# doogie_bottom_board.net
KiCad netlist of a schematic drawn in EAGLE
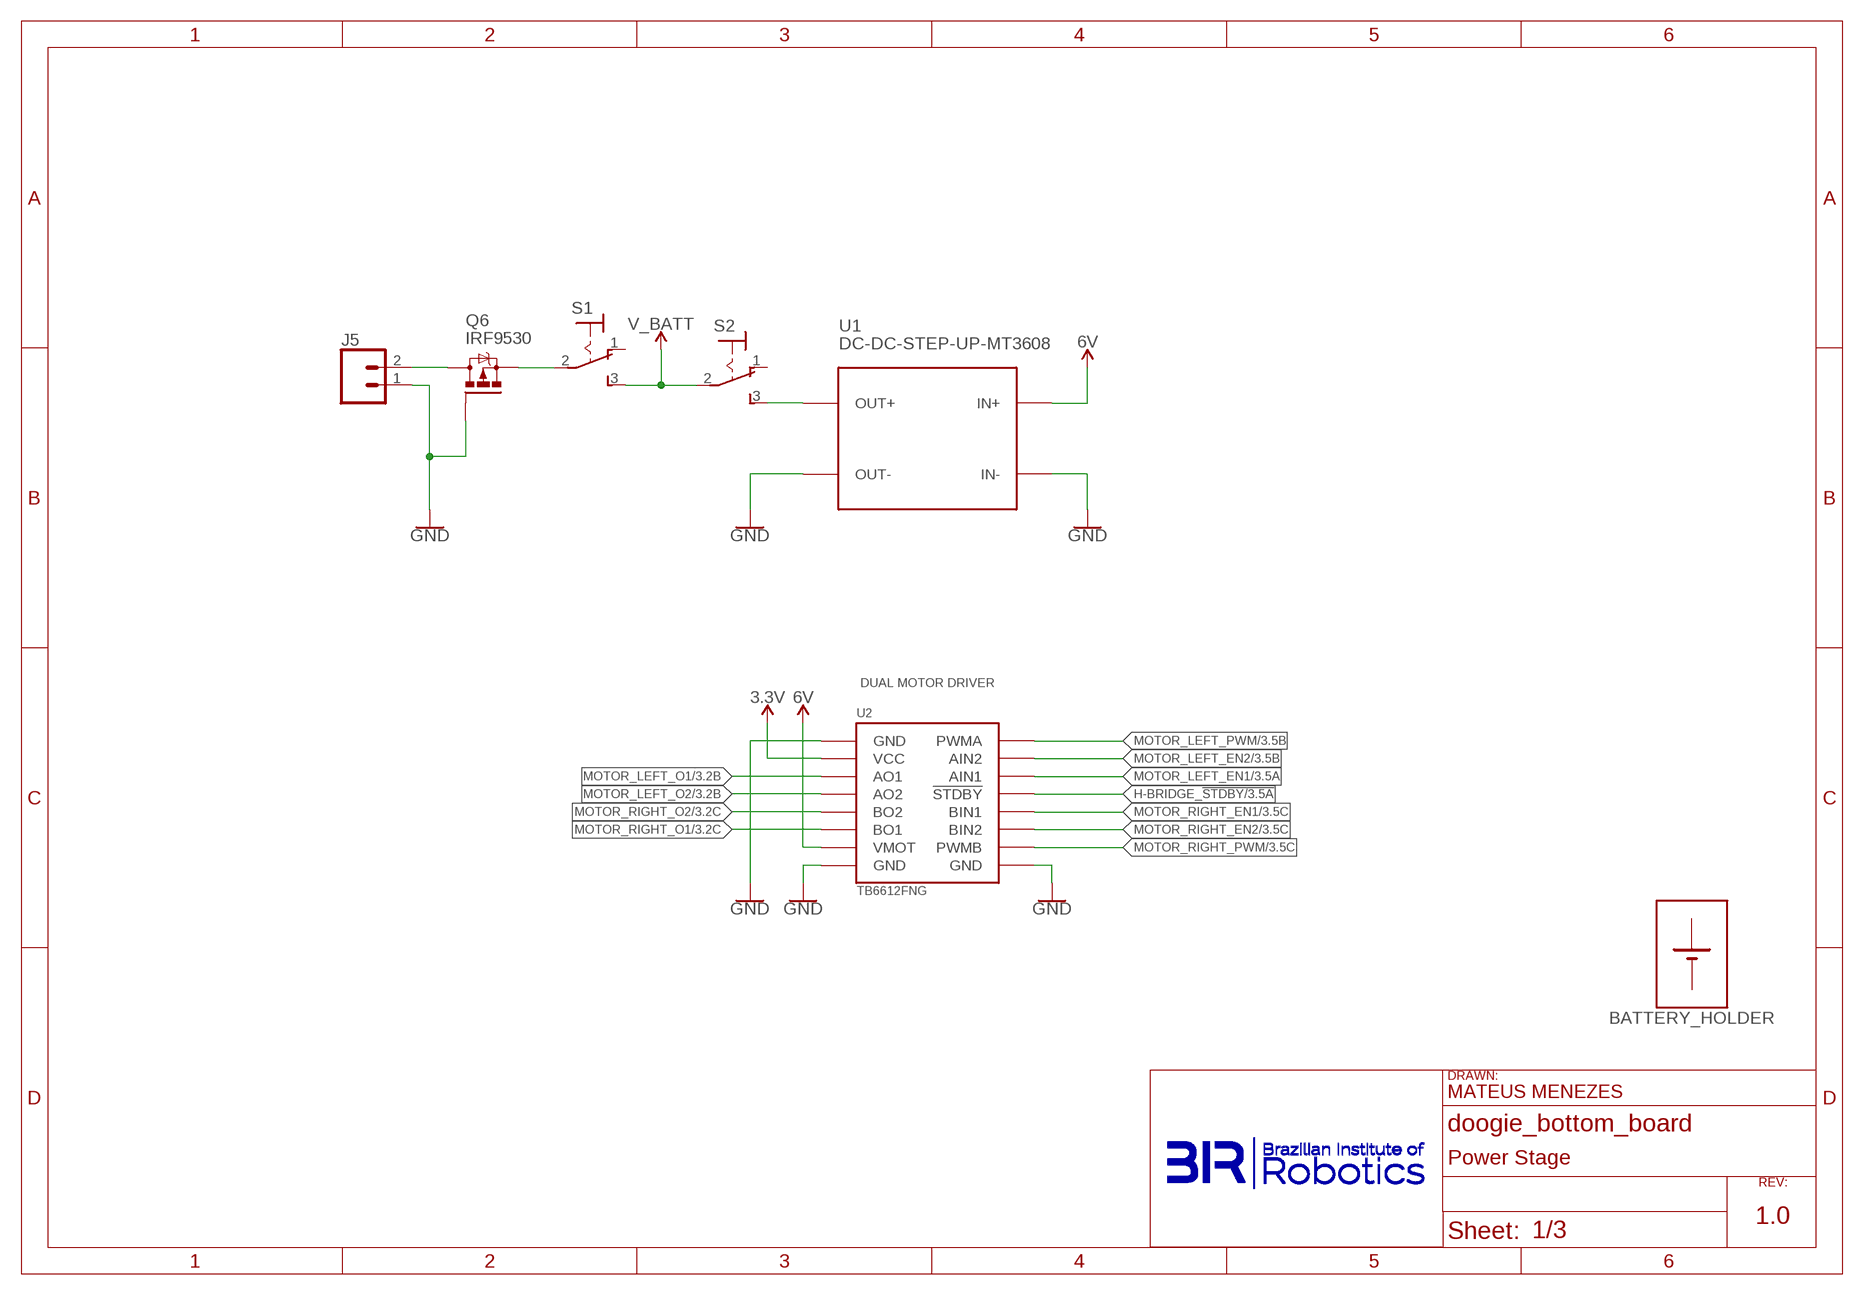
[diagram p0: schematic, sheet 1]
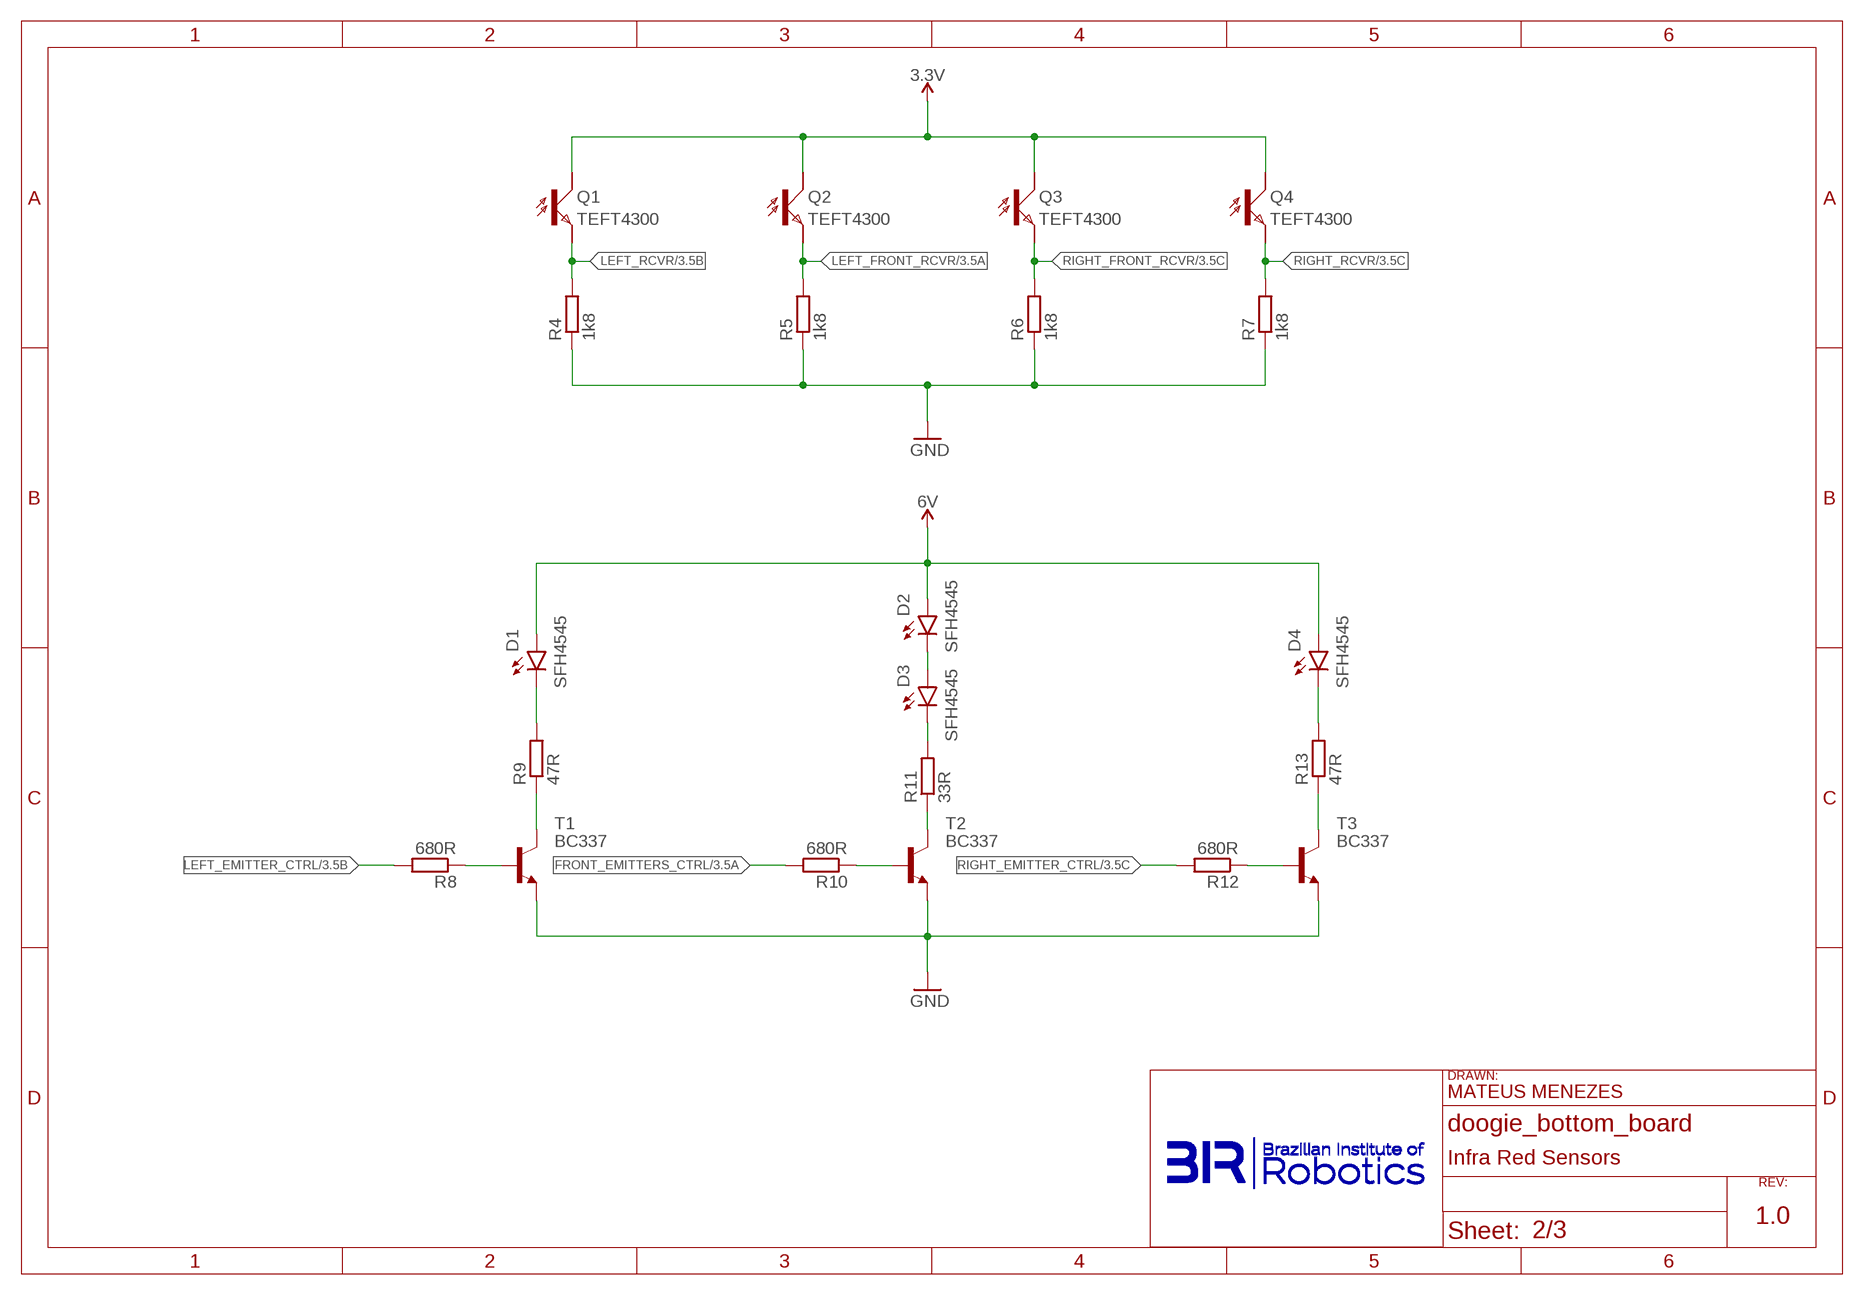
[diagram p1: schematic, sheet 2]
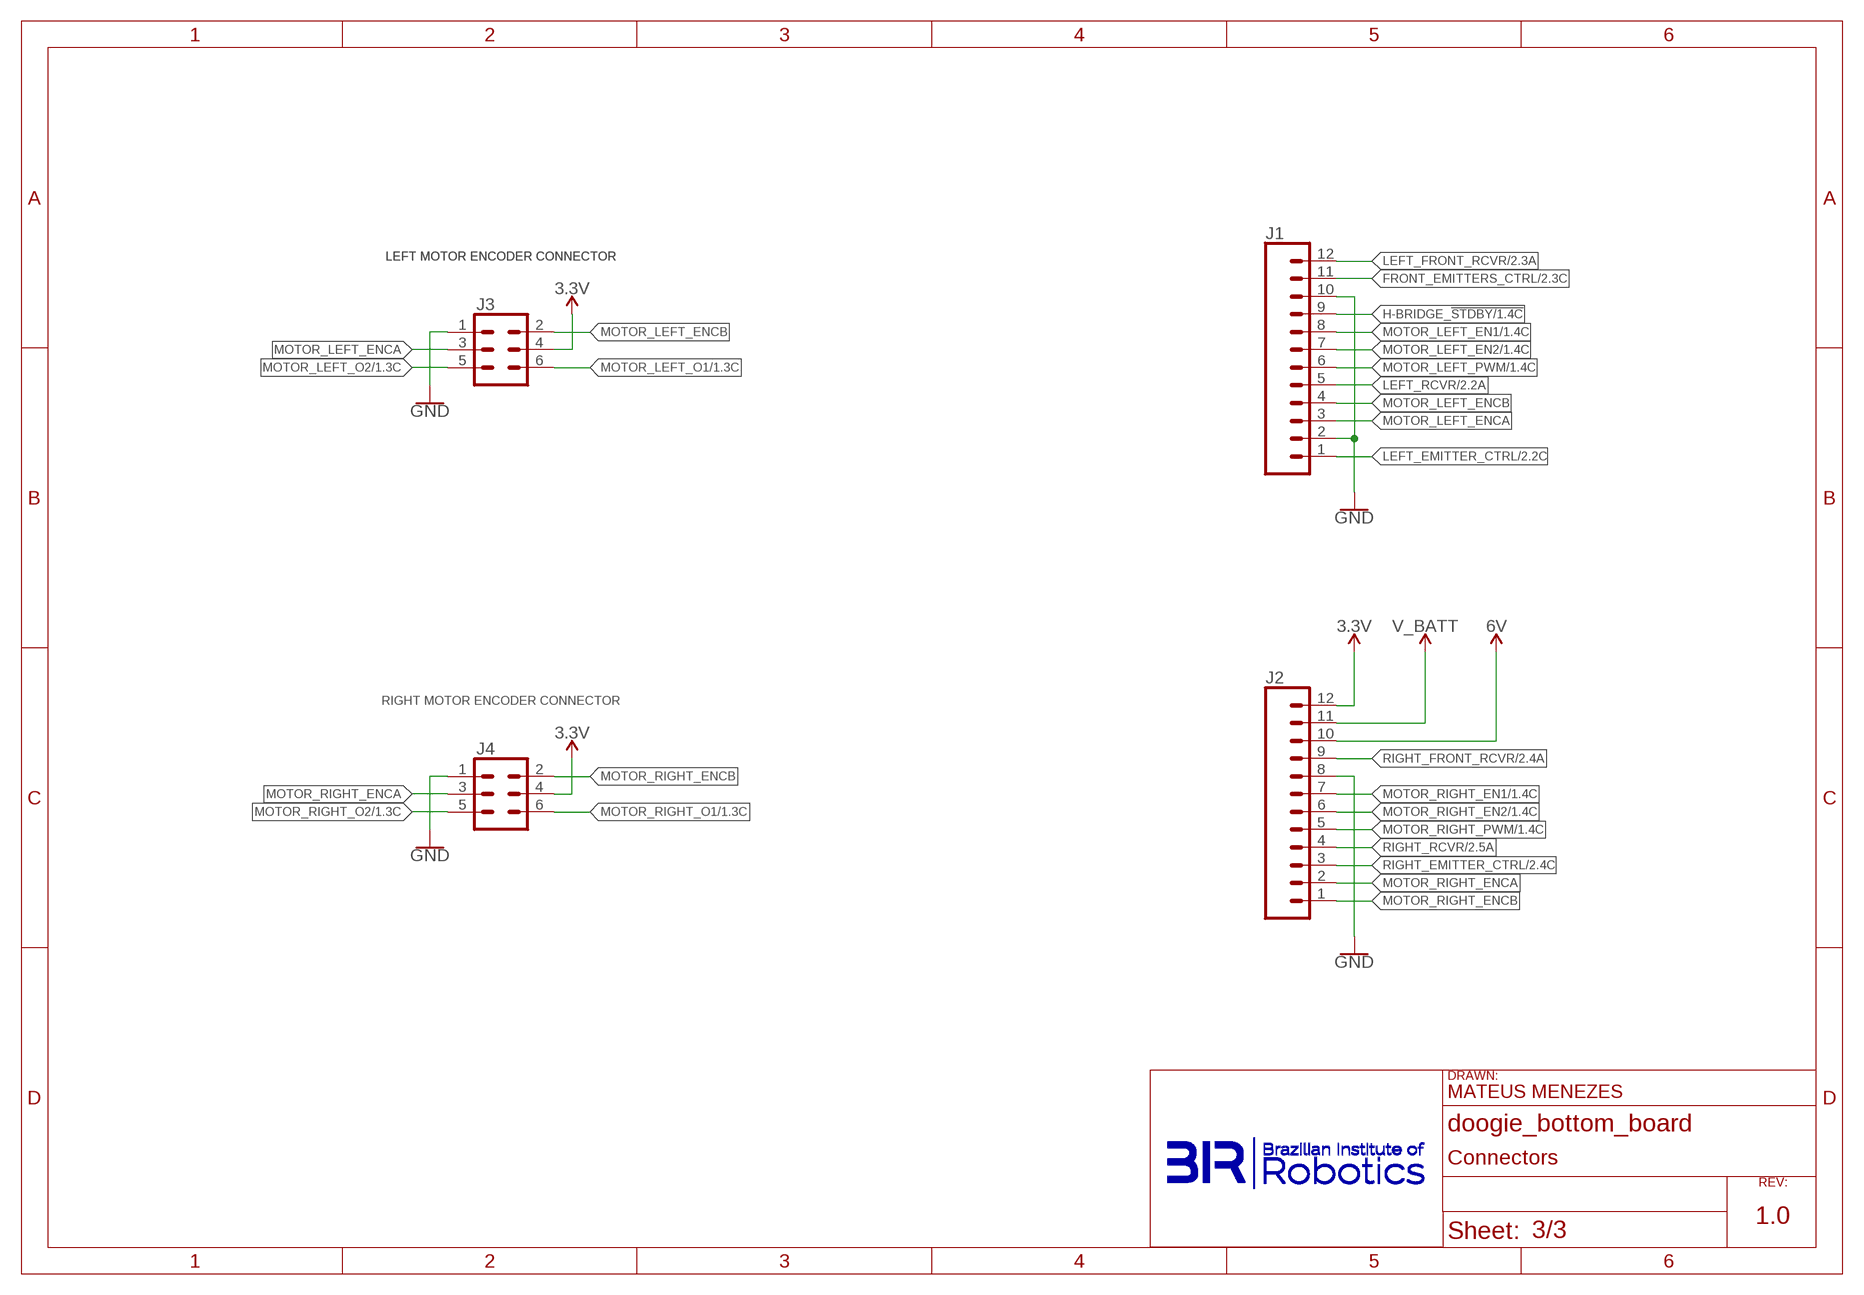
[diagram p2: schematic, sheet 3]

(export (version "E")
  (design (tool "Eeschema 10.0.6"))
  (components
    (comp (ref "D1")
      (value "SFH4545")
      (footprint "eagle-import:SFH4545-AK")
      (libsource (lib "eagle-import") (part "SFH4545"))
    )
    (comp (ref "D2")
      (value "SFH4545")
      (footprint "eagle-import:SFH4545-AK")
      (libsource (lib "eagle-import") (part "SFH4545"))
    )
    (comp (ref "D3")
      (value "SFH4545")
      (footprint "eagle-import:SFH4545-AK")
      (libsource (lib "eagle-import") (part "SFH4545"))
    )
    (comp (ref "D4")
      (value "SFH4545")
      (footprint "eagle-import:SFH4545-AK")
      (libsource (lib "eagle-import") (part "SFH4545"))
    )
    (comp (ref "Q1")
      (value "TEFT4300")
      (footprint "eagle-import:TEFT_5MM_RA")
      (libsource (lib "eagle-import") (part "TEFT4300_5MM_RA"))
    )
    (comp (ref "Q2")
      (value "TEFT4300")
      (footprint "eagle-import:TEFT_5MM_RA")
      (libsource (lib "eagle-import") (part "TEFT4300_5MM_RA"))
    )
    (comp (ref "Q3")
      (value "TEFT4300")
      (footprint "eagle-import:TEFT_5MM_RA")
      (libsource (lib "eagle-import") (part "TEFT4300_5MM_RA"))
    )
    (comp (ref "Q4")
      (value "TEFT4300")
      (footprint "eagle-import:TEFT_5MM_RA")
      (libsource (lib "eagle-import") (part "TEFT4300_5MM_RA"))
    )
    (comp (ref "R4")
      (value "1k8")
      (footprint "eagle-import:0204_7")
      (libsource (lib "eagle-import") (part "R-EU_0204/7"))
    )
    (comp (ref "R5")
      (value "1k8")
      (footprint "eagle-import:0204_7")
      (libsource (lib "eagle-import") (part "R-EU_0204/7"))
    )
    (comp (ref "R6")
      (value "1k8")
      (footprint "eagle-import:0204_7")
      (libsource (lib "eagle-import") (part "R-EU_0204/7"))
    )
    (comp (ref "R7")
      (value "1k8")
      (footprint "eagle-import:0204_7")
      (libsource (lib "eagle-import") (part "R-EU_0204/7"))
    )
    (comp (ref "R8")
      (value "680R")
      (footprint "eagle-import:0204_7")
      (libsource (lib "eagle-import") (part "R-EU_0204/7"))
    )
    (comp (ref "R9")
      (value "47R")
      (footprint "eagle-import:0204_7")
      (libsource (lib "eagle-import") (part "R-EU_0204/7"))
    )
    (comp (ref "R10")
      (value "680R")
      (footprint "eagle-import:0204_7")
      (libsource (lib "eagle-import") (part "R-EU_0204/7"))
    )
    (comp (ref "R11")
      (value "33R")
      (footprint "eagle-import:0204_7")
      (libsource (lib "eagle-import") (part "R-EU_0204/7"))
    )
    (comp (ref "R12")
      (value "680R")
      (footprint "eagle-import:0204_7")
      (libsource (lib "eagle-import") (part "R-EU_0204/7"))
    )
    (comp (ref "R13")
      (value "47R")
      (footprint "eagle-import:0204_7")
      (libsource (lib "eagle-import") (part "R-EU_0204/7"))
    )
    (comp (ref "T1")
      (value "BC337")
      (footprint "eagle-import:TO92")
      (libsource (lib "eagle-import") (part "BC337"))
    )
    (comp (ref "T2")
      (value "BC337")
      (footprint "eagle-import:TO92")
      (libsource (lib "eagle-import") (part "BC337"))
    )
    (comp (ref "T3")
      (value "BC337")
      (footprint "eagle-import:TO92")
      (libsource (lib "eagle-import") (part "BC337"))
    )
    (comp (ref "BATTERY_HOLDER")
      (value "BATTERY_HOLDER")
      (footprint "eagle-import:BATTERY_HOLDER")
      (libsource (lib "eagle-import") (part "BATTERY_HOLDER"))
    )
    (comp (ref "J5")
      (value "CONN_02JST-PTH-2")
      (footprint "eagle-import:JST-2-PTH")
      (libsource (lib "eagle-import") (part "CONN_02JST-PTH-2"))
    )
    (comp (ref "Q6")
      (value "IRF9530")
      (footprint "eagle-import:TO220BV")
      (libsource (lib "eagle-import") (part "IRF9530"))
    )
    (comp (ref "S1")
      (value "M9040P")
      (footprint "eagle-import:M9040P")
      (libsource (lib "eagle-import") (part "M9040P"))
    )
    (comp (ref "S2")
      (value "M9040P")
      (footprint "eagle-import:M9040P")
      (libsource (lib "eagle-import") (part "M9040P"))
    )
    (comp (ref "U1")
      (value "DC-DC-STEP-UP-MT3608")
      (footprint "eagle-import:DC-DC-STEP-UP-MT3608")
      (libsource (lib "eagle-import") (part "DC-DC-STEP-UP-MT3608"))
    )
    (comp (ref "U2")
      (value "TB6612FNG")
      (footprint "eagle-import:TB6612FNG")
      (libsource (lib "eagle-import") (part "TB6612FNG"))
    )
    (comp (ref "J1")
      (value "CONN_12")
      (footprint "eagle-import:1X12")
      (libsource (lib "eagle-import") (part "CONN_12"))
    )
    (comp (ref "J2")
      (value "CONN_12")
      (footprint "eagle-import:1X12")
      (libsource (lib "eagle-import") (part "CONN_12"))
    )
    (comp (ref "J3")
      (value "CONN_03X2SHROUD")
      (footprint "eagle-import:2X3-SHROUDED")
      (libsource (lib "eagle-import") (part "CONN_03X2SHROUD"))
    )
    (comp (ref "J4")
      (value "CONN_03X2SHROUD")
      (footprint "eagle-import:2X3-SHROUDED")
      (libsource (lib "eagle-import") (part "CONN_03X2SHROUD"))
    )
  )
  (nets
    (net (code "1") (name "3.3V") (class "Default")
      (node (ref "J2") (pin "12") (pinfunction "12_12") (pintype "passive"))
      (node (ref "J3") (pin "4") (pinfunction "4_4") (pintype "bidirectional"))
      (node (ref "J4") (pin "4") (pinfunction "4_4") (pintype "bidirectional"))
      (node (ref "Q1") (pin "C") (pinfunction "C_C") (pintype "passive"))
      (node (ref "Q2") (pin "C") (pinfunction "C_C") (pintype "passive"))
      (node (ref "Q3") (pin "C") (pinfunction "C_C") (pintype "passive"))
      (node (ref "Q4") (pin "C") (pinfunction "C_C") (pintype "passive"))
      (node (ref "U2") (pin "2") (pinfunction "VCC_2") (pintype "power_in"))
    )
    (net (code "2") (name "6V") (class "Default")
      (node (ref "D1") (pin "A") (pinfunction "A_A") (pintype "passive"))
      (node (ref "D2") (pin "A") (pinfunction "A_A") (pintype "passive"))
      (node (ref "D4") (pin "A") (pinfunction "A_A") (pintype "passive"))
      (node (ref "J2") (pin "10") (pinfunction "10_10") (pintype "passive"))
      (node (ref "U1") (pin "IN+") (pinfunction "IN+_IN+") (pintype "bidirectional"))
      (node (ref "U2") (pin "7") (pinfunction "VMOT_7") (pintype "power_in"))
    )
    (net (code "3") (name "FRONT_EMITTERS_CTRL") (class "Default")
      (node (ref "J1") (pin "11") (pinfunction "11_11") (pintype "passive"))
      (node (ref "R10") (pin "2") (pinfunction "2_2") (pintype "passive"))
    )
    (net (code "4") (name "GND") (class "Default")
      (node (ref "J1") (pin "10") (pinfunction "10_10") (pintype "passive"))
      (node (ref "J1") (pin "2") (pinfunction "2_2") (pintype "passive"))
      (node (ref "J2") (pin "8") (pinfunction "8_8") (pintype "passive"))
      (node (ref "J3") (pin "1") (pinfunction "1_1") (pintype "bidirectional"))
      (node (ref "J4") (pin "1") (pinfunction "1_1") (pintype "bidirectional"))
      (node (ref "J5") (pin "1") (pinfunction "1_1") (pintype "passive"))
      (node (ref "Q6") (pin "G") (pinfunction "G_G") (pintype "passive"))
      (node (ref "R4") (pin "1") (pinfunction "1_1") (pintype "passive"))
      (node (ref "R5") (pin "1") (pinfunction "1_1") (pintype "passive"))
      (node (ref "R6") (pin "1") (pinfunction "1_1") (pintype "passive"))
      (node (ref "R7") (pin "1") (pinfunction "1_1") (pintype "passive"))
      (node (ref "T1") (pin "1") (pinfunction "E_1") (pintype "passive"))
      (node (ref "T2") (pin "1") (pinfunction "E_1") (pintype "passive"))
      (node (ref "T3") (pin "1") (pinfunction "E_1") (pintype "passive"))
      (node (ref "U1") (pin "IN-") (pinfunction "IN-_IN-") (pintype "bidirectional"))
      (node (ref "U1") (pin "OUT-") (pinfunction "OUT-_OUT-") (pintype "bidirectional"))
      (node (ref "U2") (pin "1") (pinfunction "GND_1") (pintype "power_in"))
      (node (ref "U2") (pin "16") (pinfunction "GND_16") (pintype "power_in"))
      (node (ref "U2") (pin "8") (pinfunction "GND_8") (pintype "power_in"))
    )
    (net (code "5") (name "H-BRIDGE_~{STDBY}") (class "Default")
      (node (ref "J1") (pin "9") (pinfunction "9_9") (pintype "passive"))
      (node (ref "U2") (pin "12") (pinfunction "~{STDBY}_12") (pintype "input"))
    )
    (net (code "6") (name "LEFT_EMITTER_CTRL") (class "Default")
      (node (ref "J1") (pin "1") (pinfunction "1_1") (pintype "passive"))
      (node (ref "R8") (pin "2") (pinfunction "2_2") (pintype "passive"))
    )
    (net (code "7") (name "LEFT_FRONT_RCVR") (class "Default")
      (node (ref "J1") (pin "12") (pinfunction "12_12") (pintype "passive"))
      (node (ref "Q2") (pin "E") (pinfunction "E_E") (pintype "passive"))
      (node (ref "R5") (pin "2") (pinfunction "2_2") (pintype "passive"))
    )
    (net (code "8") (name "LEFT_RCVR") (class "Default")
      (node (ref "J1") (pin "5") (pinfunction "5_5") (pintype "passive"))
      (node (ref "Q1") (pin "E") (pinfunction "E_E") (pintype "passive"))
      (node (ref "R4") (pin "2") (pinfunction "2_2") (pintype "passive"))
    )
    (net (code "9") (name "MOTOR_LEFT_EN1") (class "Default")
      (node (ref "J1") (pin "8") (pinfunction "8_8") (pintype "passive"))
      (node (ref "U2") (pin "11") (pinfunction "AIN1_11") (pintype "input"))
    )
    (net (code "10") (name "MOTOR_LEFT_EN2") (class "Default")
      (node (ref "J1") (pin "7") (pinfunction "7_7") (pintype "passive"))
      (node (ref "U2") (pin "10") (pinfunction "AIN2_10") (pintype "input"))
    )
    (net (code "11") (name "MOTOR_LEFT_ENCA") (class "Default")
      (node (ref "J1") (pin "3") (pinfunction "3_3") (pintype "passive"))
      (node (ref "J3") (pin "3") (pinfunction "3_3") (pintype "bidirectional"))
    )
    (net (code "12") (name "MOTOR_LEFT_ENCB") (class "Default")
      (node (ref "J1") (pin "4") (pinfunction "4_4") (pintype "passive"))
      (node (ref "J3") (pin "2") (pinfunction "2_2") (pintype "bidirectional"))
    )
    (net (code "13") (name "MOTOR_LEFT_O1") (class "Default")
      (node (ref "J3") (pin "6") (pinfunction "6_6") (pintype "bidirectional"))
      (node (ref "U2") (pin "3") (pinfunction "AO1_3") (pintype "output"))
    )
    (net (code "14") (name "MOTOR_LEFT_O2") (class "Default")
      (node (ref "J3") (pin "5") (pinfunction "5_5") (pintype "bidirectional"))
      (node (ref "U2") (pin "4") (pinfunction "AO2_4") (pintype "output"))
    )
    (net (code "15") (name "MOTOR_LEFT_PWM") (class "Default")
      (node (ref "J1") (pin "6") (pinfunction "6_6") (pintype "passive"))
      (node (ref "U2") (pin "9") (pinfunction "PWMA_9") (pintype "input"))
    )
    (net (code "16") (name "MOTOR_RIGHT_EN1") (class "Default")
      (node (ref "J2") (pin "7") (pinfunction "7_7") (pintype "passive"))
      (node (ref "U2") (pin "13") (pinfunction "BIN1_13") (pintype "input"))
    )
    (net (code "17") (name "MOTOR_RIGHT_EN2") (class "Default")
      (node (ref "J2") (pin "6") (pinfunction "6_6") (pintype "passive"))
      (node (ref "U2") (pin "14") (pinfunction "BIN2_14") (pintype "input"))
    )
    (net (code "18") (name "MOTOR_RIGHT_ENCA") (class "Default")
      (node (ref "J2") (pin "2") (pinfunction "2_2") (pintype "passive"))
      (node (ref "J4") (pin "3") (pinfunction "3_3") (pintype "bidirectional"))
    )
    (net (code "19") (name "MOTOR_RIGHT_ENCB") (class "Default")
      (node (ref "J2") (pin "1") (pinfunction "1_1") (pintype "passive"))
      (node (ref "J4") (pin "2") (pinfunction "2_2") (pintype "bidirectional"))
    )
    (net (code "20") (name "MOTOR_RIGHT_O1") (class "Default")
      (node (ref "J4") (pin "6") (pinfunction "6_6") (pintype "bidirectional"))
      (node (ref "U2") (pin "6") (pinfunction "BO1_6") (pintype "output"))
    )
    (net (code "21") (name "MOTOR_RIGHT_O2") (class "Default")
      (node (ref "J4") (pin "5") (pinfunction "5_5") (pintype "bidirectional"))
      (node (ref "U2") (pin "5") (pinfunction "BO2_5") (pintype "output"))
    )
    (net (code "22") (name "MOTOR_RIGHT_PWM") (class "Default")
      (node (ref "J2") (pin "5") (pinfunction "5_5") (pintype "passive"))
      (node (ref "U2") (pin "15") (pinfunction "PWMB_15") (pintype "input"))
    )
    (net (code "23") (name "Net-(D1-C)") (class "Default")
      (node (ref "D1") (pin "K") (pinfunction "C_K") (pintype "passive"))
      (node (ref "R9") (pin "2") (pinfunction "2_2") (pintype "passive"))
    )
    (net (code "24") (name "Net-(D2-C)") (class "Default")
      (node (ref "D2") (pin "K") (pinfunction "C_K") (pintype "passive"))
      (node (ref "D3") (pin "A") (pinfunction "A_A") (pintype "passive"))
    )
    (net (code "25") (name "Net-(D3-C)") (class "Default")
      (node (ref "D3") (pin "K") (pinfunction "C_K") (pintype "passive"))
      (node (ref "R11") (pin "2") (pinfunction "2_2") (pintype "passive"))
    )
    (net (code "26") (name "Net-(D4-C)") (class "Default")
      (node (ref "D4") (pin "K") (pinfunction "C_K") (pintype "passive"))
      (node (ref "R13") (pin "2") (pinfunction "2_2") (pintype "passive"))
    )
    (net (code "27") (name "Net-(J5-Pad2)") (class "Default")
      (node (ref "J5") (pin "2") (pinfunction "2_2") (pintype "passive"))
      (node (ref "Q6") (pin "D") (pinfunction "D_D") (pintype "passive"))
    )
    (net (code "28") (name "Net-(S1-P)") (class "Default")
      (node (ref "Q6") (pin "S") (pinfunction "S_S") (pintype "passive"))
      (node (ref "S1") (pin "2") (pinfunction "P_2") (pintype "passive"))
    )
    (net (code "29") (name "Net-(S2-S)") (class "Default")
      (node (ref "S2") (pin "3") (pinfunction "S_3") (pintype "passive"))
      (node (ref "U1") (pin "OUT+") (pinfunction "OUT+_OUT+") (pintype "bidirectional"))
    )
    (net (code "30") (name "Net-(T1-B)") (class "Default")
      (node (ref "R8") (pin "1") (pinfunction "1_1") (pintype "passive"))
      (node (ref "T1") (pin "2") (pinfunction "B_2") (pintype "passive"))
    )
    (net (code "31") (name "Net-(T1-C)") (class "Default")
      (node (ref "R9") (pin "1") (pinfunction "1_1") (pintype "passive"))
      (node (ref "T1") (pin "3") (pinfunction "C_3") (pintype "passive"))
    )
    (net (code "32") (name "Net-(T2-B)") (class "Default")
      (node (ref "R10") (pin "1") (pinfunction "1_1") (pintype "passive"))
      (node (ref "T2") (pin "2") (pinfunction "B_2") (pintype "passive"))
    )
    (net (code "33") (name "Net-(T2-C)") (class "Default")
      (node (ref "R11") (pin "1") (pinfunction "1_1") (pintype "passive"))
      (node (ref "T2") (pin "3") (pinfunction "C_3") (pintype "passive"))
    )
    (net (code "34") (name "Net-(T3-B)") (class "Default")
      (node (ref "R12") (pin "1") (pinfunction "1_1") (pintype "passive"))
      (node (ref "T3") (pin "2") (pinfunction "B_2") (pintype "passive"))
    )
    (net (code "35") (name "Net-(T3-C)") (class "Default")
      (node (ref "R13") (pin "1") (pinfunction "1_1") (pintype "passive"))
      (node (ref "T3") (pin "3") (pinfunction "C_3") (pintype "passive"))
    )
    (net (code "36") (name "RIGHT_EMITTER_CTRL") (class "Default")
      (node (ref "J2") (pin "3") (pinfunction "3_3") (pintype "passive"))
      (node (ref "R12") (pin "2") (pinfunction "2_2") (pintype "passive"))
    )
    (net (code "37") (name "RIGHT_FRONT_RCVR") (class "Default")
      (node (ref "J2") (pin "9") (pinfunction "9_9") (pintype "passive"))
      (node (ref "Q3") (pin "E") (pinfunction "E_E") (pintype "passive"))
      (node (ref "R6") (pin "2") (pinfunction "2_2") (pintype "passive"))
    )
    (net (code "38") (name "RIGHT_RCVR") (class "Default")
      (node (ref "J2") (pin "4") (pinfunction "4_4") (pintype "passive"))
      (node (ref "Q4") (pin "E") (pinfunction "E_E") (pintype "passive"))
      (node (ref "R7") (pin "2") (pinfunction "2_2") (pintype "passive"))
    )
    (net (code "39") (name "V_BATT") (class "Default")
      (node (ref "J2") (pin "11") (pinfunction "11_11") (pintype "passive"))
      (node (ref "S1") (pin "3") (pinfunction "S_3") (pintype "passive"))
      (node (ref "S2") (pin "2") (pinfunction "P_2") (pintype "passive"))
    )
    (net (code "40") (name "unconnected-(S1-O-Pad1)") (class "Default")
      (node (ref "S1") (pin "1") (pinfunction "O_1") (pintype "passive"))
    )
    (net (code "41") (name "unconnected-(S2-O-Pad1)") (class "Default")
      (node (ref "S2") (pin "1") (pinfunction "O_1") (pintype "passive"))
    )
  )
)
